# UVicorn-kit.net
KiCad netlist of a schematic drawn in EAGLE
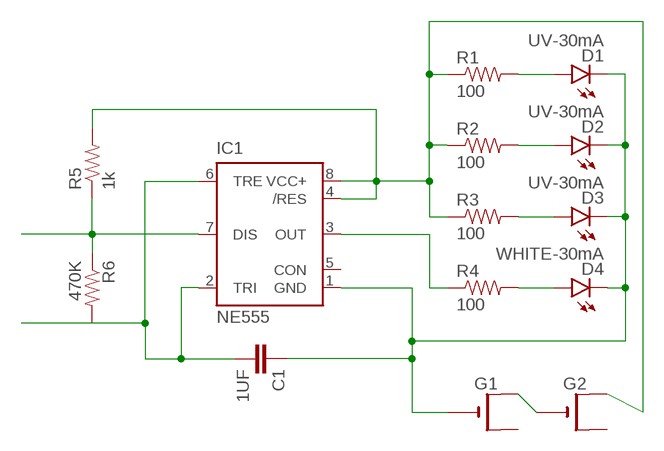
[diagram p0: schematic, sheet 1]

(export (version "E")
  (design (tool "Eeschema 10.0.6"))
  (components
    (comp (ref "C1")
      (value "1UF")
      (footprint "eagle-import:AXIAL-5MM")
      (libsource (lib "eagle-import") (part "CAP_"))
    )
    (comp (ref "D1")
      (value "UV-30mA")
      (footprint "eagle-import:LED5MM_ANYSIDES")
      (libsource (lib "eagle-import") (part "LED"))
    )
    (comp (ref "D2")
      (value "UV-30mA")
      (footprint "eagle-import:LED5MM_ANYSIDES")
      (libsource (lib "eagle-import") (part "LED"))
    )
    (comp (ref "D3")
      (value "UV-30mA")
      (footprint "eagle-import:LED5MM_ANYSIDES")
      (libsource (lib "eagle-import") (part "LED"))
    )
    (comp (ref "D4")
      (value "WHITE-30mA")
      (footprint "eagle-import:LED5MM_ANYSIDES")
      (libsource (lib "eagle-import") (part "LED"))
    )
    (comp (ref "G1")
      (value "CR2032")
      (footprint "eagle-import:CR2032-EDIT")
      (libsource (lib "eagle-import") (part "CR2032"))
    )
    (comp (ref "G2")
      (value "CR2032")
      (footprint "eagle-import:CR2032-EDIT")
      (libsource (lib "eagle-import") (part "CR2032"))
    )
    (comp (ref "IC1")
      (value "NE555")
      (footprint "eagle-import:DIL-08")
      (fields (field (name "MF") "Arrow Electronics") (field (name "MPN") "NE555N"))
      (libsource (lib "eagle-import") (part "NE555"))
    )
    (comp (ref "R1")
      (value "100")
      (footprint "eagle-import:AXIAL-0.3EZ")
      (libsource (lib "eagle-import") (part "1KOHM-1/4W-5%(PTH)HORIZ-KIT"))
    )
    (comp (ref "R2")
      (value "100")
      (footprint "eagle-import:AXIAL-0.3EZ")
      (libsource (lib "eagle-import") (part "1KOHM-1/4W-5%(PTH)HORIZ-KIT"))
    )
    (comp (ref "R3")
      (value "100")
      (footprint "eagle-import:AXIAL-0.3EZ")
      (libsource (lib "eagle-import") (part "1KOHM-1/4W-5%(PTH)HORIZ-KIT"))
    )
    (comp (ref "R4")
      (value "100")
      (footprint "eagle-import:AXIAL-0.3EZ")
      (libsource (lib "eagle-import") (part "1KOHM-1/4W-5%(PTH)HORIZ-KIT"))
    )
    (comp (ref "R5")
      (value "1k")
      (footprint "eagle-import:AXIAL-0.3EZ")
      (libsource (lib "eagle-import") (part "1KOHM-1/4W-5%(PTH)HORIZ-KIT"))
    )
    (comp (ref "R6")
      (value "470K")
      (footprint "eagle-import:AXIAL-0.3EZ")
      (libsource (lib "eagle-import") (part "1KOHM-1/4W-5%(PTH)HORIZ-KIT"))
    )
  )
  (nets
    (net (code "1") (name "Net-(C1-1)") (class "Default")
      (node (ref "C1") (pin "P$1") (pinfunction "1_P$1") (pintype "passive"))
      (node (ref "D1") (pin "K") (pinfunction "C_K") (pintype "passive"))
      (node (ref "D2") (pin "K") (pinfunction "C_K") (pintype "passive"))
      (node (ref "D3") (pin "K") (pinfunction "C_K") (pintype "passive"))
      (node (ref "D4") (pin "K") (pinfunction "C_K") (pintype "passive"))
      (node (ref "G1") (pin "-") (pinfunction "-_-") (pintype "passive"))
      (node (ref "IC1") (pin "1") (pinfunction "GND_1") (pintype "power_in"))
    )
    (net (code "2") (name "Net-(C1-2)") (class "Default")
      (node (ref "C1") (pin "P$2") (pinfunction "2_P$2") (pintype "passive"))
      (node (ref "IC1") (pin "2") (pinfunction "TRI_2") (pintype "input"))
      (node (ref "IC1") (pin "6") (pinfunction "TRE_6") (pintype "input"))
      (node (ref "R6") (pin "P$2") (pinfunction "2_P$2") (pintype "passive"))
    )
    (net (code "3") (name "Net-(G1-+)") (class "Default")
      (node (ref "G1") (pin "+1") (pinfunction "+_+1") (pintype "passive"))
      (node (ref "G2") (pin "-") (pinfunction "-_-") (pintype "passive"))
    )
    (net (code "4") (name "Net-(G2-+)") (class "Default")
      (node (ref "G2") (pin "+1") (pinfunction "+_+1") (pintype "passive"))
      (node (ref "IC1") (pin "4") (pinfunction "/RES_4") (pintype "input"))
      (node (ref "IC1") (pin "8") (pinfunction "VCC+_8") (pintype "power_in"))
      (node (ref "R1") (pin "P$1") (pinfunction "1_P$1") (pintype "passive"))
      (node (ref "R2") (pin "P$1") (pinfunction "1_P$1") (pintype "passive"))
      (node (ref "R3") (pin "P$1") (pinfunction "1_P$1") (pintype "passive"))
      (node (ref "R5") (pin "P$2") (pinfunction "2_P$2") (pintype "passive"))
    )
    (net (code "5") (name "Net-(IC1-DIS)") (class "Default")
      (node (ref "IC1") (pin "7") (pinfunction "DIS_7") (pintype "input"))
      (node (ref "R5") (pin "P$1") (pinfunction "1_P$1") (pintype "passive"))
      (node (ref "R6") (pin "P$1") (pinfunction "1_P$1") (pintype "passive"))
    )
    (net (code "6") (name "Net-(IC1-OUT)") (class "Default")
      (node (ref "IC1") (pin "3") (pinfunction "OUT_3") (pintype "output"))
      (node (ref "R4") (pin "P$1") (pinfunction "1_P$1") (pintype "passive"))
    )
    (net (code "7") (name "Net-(R1-2)") (class "Default")
      (node (ref "D1") (pin "A") (pinfunction "A_A") (pintype "passive"))
      (node (ref "R1") (pin "P$2") (pinfunction "2_P$2") (pintype "passive"))
    )
    (net (code "8") (name "Net-(R2-2)") (class "Default")
      (node (ref "D2") (pin "A") (pinfunction "A_A") (pintype "passive"))
      (node (ref "R2") (pin "P$2") (pinfunction "2_P$2") (pintype "passive"))
    )
    (net (code "9") (name "Net-(R3-2)") (class "Default")
      (node (ref "D3") (pin "A") (pinfunction "A_A") (pintype "passive"))
      (node (ref "R3") (pin "P$2") (pinfunction "2_P$2") (pintype "passive"))
    )
    (net (code "10") (name "Net-(R4-2)") (class "Default")
      (node (ref "D4") (pin "A") (pinfunction "A_A") (pintype "passive"))
      (node (ref "R4") (pin "P$2") (pinfunction "2_P$2") (pintype "passive"))
    )
    (net (code "11") (name "unconnected-(G1-+1-Pad+2)") (class "Default")
      (node (ref "G1") (pin "+2") (pinfunction "+1_+2") (pintype "passive"))
    )
    (net (code "12") (name "unconnected-(G2-+1-Pad+2)") (class "Default")
      (node (ref "G2") (pin "+2") (pinfunction "+1_+2") (pintype "passive"))
    )
    (net (code "13") (name "unconnected-(IC1-CON-Pad5)") (class "Default")
      (node (ref "IC1") (pin "5") (pinfunction "CON_5") (pintype "input"))
    )
  )
)
